# horn.net
KiCad netlist of a schematic drawn in EAGLE
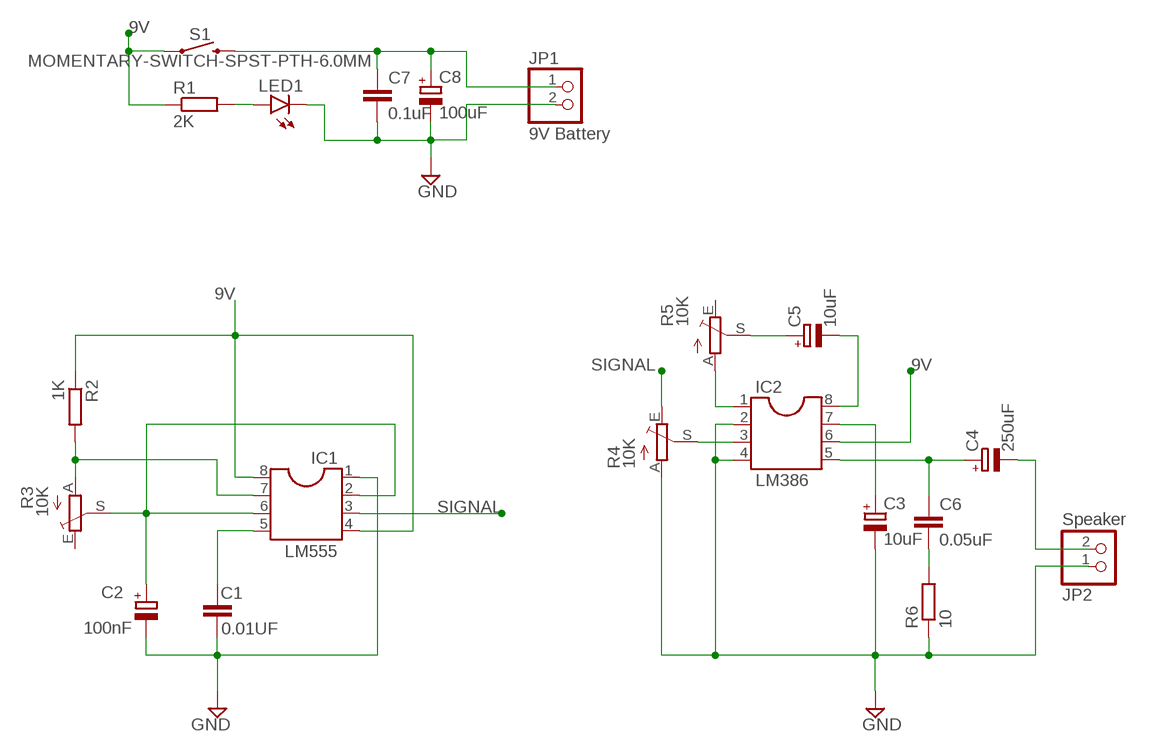
[diagram p0: schematic, sheet 1]

(export (version "E")
  (design (tool "Eeschema 10.0.6"))
  (components
    (comp (ref "C1")
      (value "0.01UF")
      (footprint "eagle-import:C025-024X044")
      (libsource (lib "eagle-import") (part "C-EU025-024X044"))
    )
    (comp (ref "C2")
      (value "100nF")
      (footprint "eagle-import:E5-5")
      (libsource (lib "eagle-import") (part "CPOL-EUE5-5"))
    )
    (comp (ref "C3")
      (value "10uF")
      (footprint "eagle-import:E5-5")
      (libsource (lib "eagle-import") (part "CPOL-EUE5-5"))
    )
    (comp (ref "C4")
      (value "250uF")
      (footprint "eagle-import:E5-5")
      (libsource (lib "eagle-import") (part "CPOL-EUE5-5"))
    )
    (comp (ref "C5")
      (value "10uF")
      (footprint "eagle-import:E5-5")
      (libsource (lib "eagle-import") (part "CPOL-EUE5-5"))
    )
    (comp (ref "C6")
      (value "0.05uF")
      (footprint "eagle-import:C025-024X044")
      (libsource (lib "eagle-import") (part "C-EU025-024X044"))
    )
    (comp (ref "C7")
      (value "0.1uF")
      (footprint "eagle-import:C025-024X044")
      (libsource (lib "eagle-import") (part "C-EU025-024X044"))
    )
    (comp (ref "C8")
      (value "100uF")
      (footprint "eagle-import:E5-5")
      (libsource (lib "eagle-import") (part "CPOL-EUE5-5"))
    )
    (comp (ref "IC1")
      (value "LM555")
      (footprint "eagle-import:SOCKET-08")
      (libsource (lib "eagle-import") (part "DIL8S"))
    )
    (comp (ref "IC2")
      (value "LM386")
      (footprint "eagle-import:SOCKET-08")
      (libsource (lib "eagle-import") (part "DIL8S"))
    )
    (comp (ref "JP1")
      (value "9V Battery")
      (footprint "eagle-import:1X02")
      (libsource (lib "eagle-import") (part "PINHD-1X2"))
    )
    (comp (ref "JP2")
      (value "Speaker")
      (footprint "eagle-import:1X02")
      (libsource (lib "eagle-import") (part "PINHD-1X2"))
    )
    (comp (ref "LED1")
      (value "LED5MM")
      (footprint "eagle-import:LED5MM")
      (libsource (lib "eagle-import") (part "LED5MM"))
    )
    (comp (ref "R1")
      (value "2K")
      (footprint "eagle-import:0204_5")
      (libsource (lib "eagle-import") (part "R-EU_0204/5"))
    )
    (comp (ref "R2")
      (value "1K")
      (footprint "eagle-import:0204_5")
      (libsource (lib "eagle-import") (part "R-EU_0204/5"))
    )
    (comp (ref "R3")
      (value "10K")
      (footprint "eagle-import:CA6V")
      (libsource (lib "eagle-import") (part "TRIM_EU-CA6V"))
    )
    (comp (ref "R4")
      (value "10K")
      (footprint "eagle-import:CA6V")
      (libsource (lib "eagle-import") (part "TRIM_EU-CA6V"))
    )
    (comp (ref "R5")
      (value "10K")
      (footprint "eagle-import:CA6V")
      (libsource (lib "eagle-import") (part "TRIM_EU-CA6V"))
    )
    (comp (ref "R6")
      (value "10")
      (footprint "eagle-import:0204_5")
      (libsource (lib "eagle-import") (part "R-EU_0204/5"))
    )
    (comp (ref "S1")
      (value "MOMENTARY-SWITCH-SPST-PTH-6.0MM")
      (footprint "eagle-import:TACTILE_SWITCH_PTH_6.0MM")
      (libsource (lib "eagle-import") (part "MOMENTARY-SWITCH-SPST-PTH-6.0MM"))
    )
  )
  (nets
    (net (code "1") (name "/9V") (class "Default")
      (node (ref "IC1") (pin "4") (pinfunction "4_4") (pintype "passive"))
      (node (ref "IC1") (pin "8") (pinfunction "8_8") (pintype "passive"))
      (node (ref "IC2") (pin "6") (pinfunction "6_6") (pintype "passive"))
      (node (ref "R1") (pin "1") (pinfunction "1_1") (pintype "passive"))
      (node (ref "R2") (pin "1") (pinfunction "1_1") (pintype "passive"))
      (node (ref "S1") (pin "1") (pinfunction "1_1") (pintype "passive"))
    )
    (net (code "2") (name "/SIGNAL") (class "Default")
      (node (ref "IC1") (pin "3") (pinfunction "3_3") (pintype "passive"))
      (node (ref "R4") (pin "E") (pinfunction "E_E") (pintype "passive"))
    )
    (net (code "3") (name "GND") (class "Default")
      (node (ref "C1") (pin "2") (pinfunction "2_2") (pintype "passive"))
      (node (ref "C2") (pin "-") (pinfunction "-_-") (pintype "passive"))
      (node (ref "C3") (pin "-") (pinfunction "-_-") (pintype "passive"))
      (node (ref "C7") (pin "2") (pinfunction "2_2") (pintype "passive"))
      (node (ref "C8") (pin "-") (pinfunction "-_-") (pintype "passive"))
      (node (ref "IC1") (pin "1") (pinfunction "1_1") (pintype "passive"))
      (node (ref "IC2") (pin "2") (pinfunction "2_2") (pintype "passive"))
      (node (ref "IC2") (pin "4") (pinfunction "4_4") (pintype "passive"))
      (node (ref "JP1") (pin "2") (pinfunction "2_2") (pintype "passive"))
      (node (ref "JP2") (pin "1") (pinfunction "1_1") (pintype "passive"))
      (node (ref "LED1") (pin "K") (pinfunction "C_K") (pintype "passive"))
      (node (ref "R4") (pin "A") (pinfunction "A_A") (pintype "passive"))
      (node (ref "R6") (pin "1") (pinfunction "1_1") (pintype "passive"))
    )
    (net (code "4") (name "Net-(C1-Pad1)") (class "Default")
      (node (ref "C1") (pin "1") (pinfunction "1_1") (pintype "passive"))
      (node (ref "IC1") (pin "5") (pinfunction "5_5") (pintype "passive"))
    )
    (net (code "5") (name "Net-(C2-Pad+)") (class "Default")
      (node (ref "C2") (pin "+") (pinfunction "+_+") (pintype "passive"))
      (node (ref "IC1") (pin "2") (pinfunction "2_2") (pintype "passive"))
      (node (ref "IC1") (pin "6") (pinfunction "6_6") (pintype "passive"))
      (node (ref "R3") (pin "S") (pinfunction "S_S") (pintype "passive"))
    )
    (net (code "6") (name "Net-(C3-Pad+)") (class "Default")
      (node (ref "C3") (pin "+") (pinfunction "+_+") (pintype "passive"))
      (node (ref "IC2") (pin "7") (pinfunction "7_7") (pintype "passive"))
    )
    (net (code "7") (name "Net-(C4-Pad+)") (class "Default")
      (node (ref "C4") (pin "+") (pinfunction "+_+") (pintype "passive"))
      (node (ref "C6") (pin "1") (pinfunction "1_1") (pintype "passive"))
      (node (ref "IC2") (pin "5") (pinfunction "5_5") (pintype "passive"))
    )
    (net (code "8") (name "Net-(C4-Pad-)") (class "Default")
      (node (ref "C4") (pin "-") (pinfunction "-_-") (pintype "passive"))
      (node (ref "JP2") (pin "2") (pinfunction "2_2") (pintype "passive"))
    )
    (net (code "9") (name "Net-(C5-Pad+)") (class "Default")
      (node (ref "C5") (pin "+") (pinfunction "+_+") (pintype "passive"))
      (node (ref "R5") (pin "S") (pinfunction "S_S") (pintype "passive"))
    )
    (net (code "10") (name "Net-(C5-Pad-)") (class "Default")
      (node (ref "C5") (pin "-") (pinfunction "-_-") (pintype "passive"))
      (node (ref "IC2") (pin "8") (pinfunction "8_8") (pintype "passive"))
    )
    (net (code "11") (name "Net-(C6-Pad2)") (class "Default")
      (node (ref "C6") (pin "2") (pinfunction "2_2") (pintype "passive"))
      (node (ref "R6") (pin "2") (pinfunction "2_2") (pintype "passive"))
    )
    (net (code "12") (name "Net-(IC1-Pad7)") (class "Default")
      (node (ref "IC1") (pin "7") (pinfunction "7_7") (pintype "passive"))
      (node (ref "R2") (pin "2") (pinfunction "2_2") (pintype "passive"))
      (node (ref "R3") (pin "A") (pinfunction "A_A") (pintype "passive"))
    )
    (net (code "13") (name "Net-(IC2-Pad1)") (class "Default")
      (node (ref "IC2") (pin "1") (pinfunction "1_1") (pintype "passive"))
      (node (ref "R5") (pin "A") (pinfunction "A_A") (pintype "passive"))
    )
    (net (code "14") (name "Net-(IC2-Pad3)") (class "Default")
      (node (ref "IC2") (pin "3") (pinfunction "3_3") (pintype "passive"))
      (node (ref "R4") (pin "S") (pinfunction "S_S") (pintype "passive"))
    )
    (net (code "15") (name "Net-(LED1-PadA)") (class "Default")
      (node (ref "LED1") (pin "A") (pinfunction "A_A") (pintype "passive"))
      (node (ref "R1") (pin "2") (pinfunction "2_2") (pintype "passive"))
    )
    (net (code "16") (name "Net-(S1-2)") (class "Default")
      (node (ref "C7") (pin "1") (pinfunction "1_1") (pintype "passive"))
      (node (ref "C8") (pin "+") (pinfunction "+_+") (pintype "passive"))
      (node (ref "JP1") (pin "1") (pinfunction "1_1") (pintype "passive"))
      (node (ref "S1") (pin "3") (pinfunction "2_3") (pintype "passive"))
    )
    (net (code "17") (name "unconnected-(R3-PadE)") (class "Default")
      (node (ref "R3") (pin "E") (pinfunction "E_E") (pintype "passive"))
    )
    (net (code "18") (name "unconnected-(R5-PadE)") (class "Default")
      (node (ref "R5") (pin "E") (pinfunction "E_E") (pintype "passive"))
    )
  )
)
